# CAN.net
KiCad netlist of a schematic drawn in Altium Designer
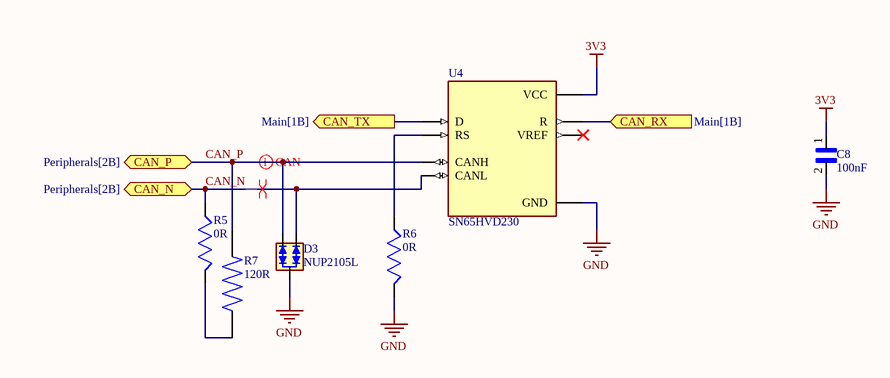
[diagram p0: CAN.SchDoc]

(export (version "E")
  (design (tool "Eeschema 10.0.6"))
  (components
    (comp (ref "C8")
      (value "100nF")
      (footprint "08055G104ZAT1A:CAPC2012X140N")
      (fields (field (name "MP") "08055G104ZAT1A") (field (name "MF") "{'manufacturer': u'AVX'}"))
      (libsource (lib "08055G104ZAT1A") (part "08055G104ZAT1A"))
    )
    (comp (ref "D3")
      (value "NUP2105L")
      (footprint "NUP2105L:SOT23")
      (fields (field (name "MF") "{'manufacturer': u'Diotec Semiconductor'}"))
      (libsource (lib "*") (part "NUP2105L"))
    )
    (comp (ref "R5")
      (value "0R")
      (footprint "RC0805JR-7W0RL:RESC2012X60")
      (description "RC Series 0805 0.125 W 2 kOhms 5% Â±100 ppm/Â°C SMT Thick Film Chip Resistor")
      (fields (field (name "MP") "RC0805JR-7W0RL") (field (name "MF") "{'manufacturer': u'Yageo'}"))
      (libsource (lib "*") (part "RC0805JR-7W0RL"))
    )
    (comp (ref "R6")
      (value "0R")
      (footprint "RC0805JR-7W0RL:RESC2012X60")
      (description "RC Series 0805 0.125 W 2 kOhms 5% Â±100 ppm/Â°C SMT Thick Film Chip Resistor")
      (fields (field (name "MP") "RC0805JR-7W0RL") (field (name "MF") "{'manufacturer': u'Yageo'}"))
      (libsource (lib "*") (part "RC0805JR-7W0RL"))
    )
    (comp (ref "R7")
      (value "120R")
      (footprint "1-2176327-4:RESC2012X65N")
      (description "Fixed Resistor CRGP 0805 120R 1%")
      (fields (field (name "MP") "1-2176327-4") (field (name "MF") "{'manufacturer': u'TE Connectivity'}"))
      (libsource (lib "*") (part "1-2176327-4"))
    )
    (comp (ref "U4")
      (value "SN65HVD230")
      (footprint "SN65HVD230:SOIC127P599X175-8N")
      (fields (field (name "MF") "{'manufacturer': u'Texas Instruments'}"))
      (libsource (lib "*") (part "SN65HVD230"))
    )
  )
  (nets
    (net (code "1") (name "/CAN_N") (class "Default")
      (node (ref "D3") (pin "1") (pinfunction "CANH_1") (pintype "bidirectional"))
      (node (ref "R5") (pin "2") (pinfunction "2_2") (pintype "passive"))
      (node (ref "U4") (pin "6") (pinfunction "CANL_6") (pintype "bidirectional"))
    )
    (net (code "2") (name "/CAN_P") (class "Default")
      (node (ref "D3") (pin "2") (pinfunction "CANL_2") (pintype "bidirectional"))
      (node (ref "R7") (pin "2") (pinfunction "2_2") (pintype "passive"))
      (node (ref "U4") (pin "7") (pinfunction "CANH_7") (pintype "bidirectional"))
    )
    (net (code "3") (name "/CAN_RX") (class "Default")
      (node (ref "U4") (pin "4") (pinfunction "R_4") (pintype "output"))
    )
    (net (code "4") (name "/CAN_TX") (class "Default")
      (node (ref "U4") (pin "1") (pinfunction "D_1") (pintype "input"))
    )
    (net (code "5") (name "3V3") (class "Default")
      (node (ref "C8") (pin "1") (pinfunction "1_1") (pintype "passive"))
      (node (ref "U4") (pin "3") (pinfunction "VCC_3") (pintype "power_in"))
    )
    (net (code "6") (name "GND") (class "Default")
      (node (ref "C8") (pin "2") (pinfunction "2_2") (pintype "passive"))
      (node (ref "D3") (pin "3") (pinfunction "GND_3") (pintype "bidirectional"))
      (node (ref "R6") (pin "1") (pinfunction "1_1") (pintype "passive"))
      (node (ref "U4") (pin "2") (pinfunction "GND_2") (pintype "power_in"))
    )
    (net (code "7") (name "Net-(R5-Pad1)") (class "Default")
      (node (ref "R5") (pin "1") (pinfunction "1_1") (pintype "passive"))
      (node (ref "R7") (pin "1") (pinfunction "1_1") (pintype "passive"))
    )
    (net (code "8") (name "Net-(U4-RS)") (class "Default")
      (node (ref "R6") (pin "2") (pinfunction "2_2") (pintype "passive"))
      (node (ref "U4") (pin "8") (pinfunction "RS_8") (pintype "input"))
    )
    (net (code "9") (name "unconnected-(U4-VREF-Pad5)") (class "Default")
      (node (ref "U4") (pin "5") (pinfunction "VREF_5") (pintype "output+no_connect"))
    )
  )
)
